# RockSat_PCB.net
KiCad netlist of a schematic drawn in EAGLE
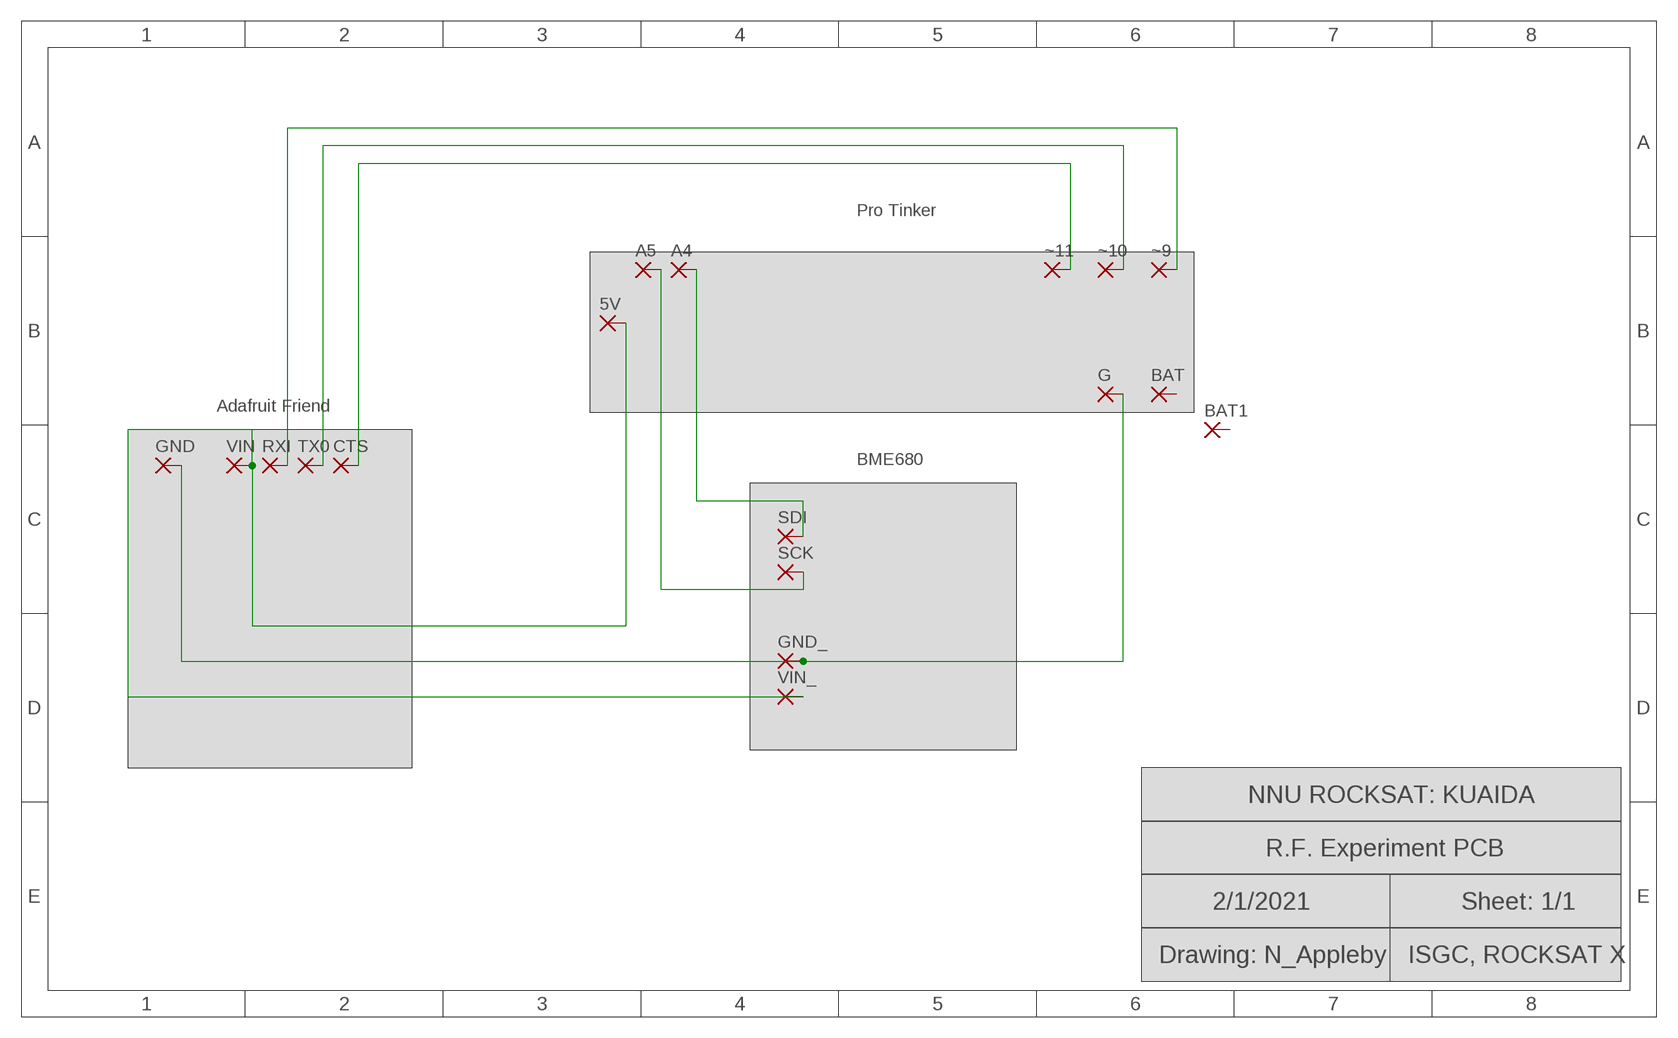
[diagram p0: schematic, sheet 1]

(export (version "E")
  (design (tool "Eeschema 10.0.6"))
  (components
    (comp (ref "5V")
      (value "1,6/0,9")
      (footprint "eagle-import:1,6_0,9")
      (libsource (lib "eagle-import") (part "1,6/0,9"))
    )
    (comp (ref "A4")
      (value "1,6/0,9")
      (footprint "eagle-import:1,6_0,9")
      (libsource (lib "eagle-import") (part "1,6/0,9"))
    )
    (comp (ref "A5")
      (value "1,6/0,9")
      (footprint "eagle-import:1,6_0,9")
      (libsource (lib "eagle-import") (part "1,6/0,9"))
    )
    (comp (ref "BAT")
      (value "1,6/0,9")
      (footprint "eagle-import:1,6_0,9")
      (libsource (lib "eagle-import") (part "1,6/0,9"))
    )
    (comp (ref "BAT1")
      (value "1,6/0,9")
      (footprint "eagle-import:1,6_0,9")
      (libsource (lib "eagle-import") (part "1,6/0,9"))
    )
    (comp (ref "CTS")
      (value "1,6/0,9")
      (footprint "eagle-import:1,6_0,9")
      (libsource (lib "eagle-import") (part "1,6/0,9"))
    )
    (comp (ref "G")
      (value "1,6/0,9")
      (footprint "eagle-import:1,6_0,9")
      (libsource (lib "eagle-import") (part "1,6/0,9"))
    )
    (comp (ref "GND")
      (value "1,6/0,9")
      (footprint "eagle-import:1,6_0,9")
      (libsource (lib "eagle-import") (part "1,6/0,9"))
    )
    (comp (ref "GND_")
      (value "1,6/0,9")
      (footprint "eagle-import:1,6_0,9")
      (libsource (lib "eagle-import") (part "1,6/0,9"))
    )
    (comp (ref "RXI")
      (value "1,6/0,9")
      (footprint "eagle-import:1,6_0,9")
      (libsource (lib "eagle-import") (part "1,6/0,9"))
    )
    (comp (ref "SCK")
      (value "1,6/0,9")
      (footprint "eagle-import:1,6_0,9")
      (libsource (lib "eagle-import") (part "1,6/0,9"))
    )
    (comp (ref "SDI")
      (value "1,6/0,9")
      (footprint "eagle-import:1,6_0,9")
      (libsource (lib "eagle-import") (part "1,6/0,9"))
    )
    (comp (ref "TX0")
      (value "1,6/0,9")
      (footprint "eagle-import:1,6_0,9")
      (libsource (lib "eagle-import") (part "1,6/0,9"))
    )
    (comp (ref "VIN")
      (value "1,6/0,9")
      (footprint "eagle-import:1,6_0,9")
      (libsource (lib "eagle-import") (part "1,6/0,9"))
    )
    (comp (ref "VIN_")
      (value "1,6/0,9")
      (footprint "eagle-import:1,6_0,9")
      (libsource (lib "eagle-import") (part "1,6/0,9"))
    )
    (comp (ref "~9")
      (value "1,6/0,9")
      (footprint "eagle-import:1,6_0,9")
      (libsource (lib "eagle-import") (part "1,6/0,9"))
    )
    (comp (ref "~10")
      (value "1,6/0,9")
      (footprint "eagle-import:1,6_0,9")
      (libsource (lib "eagle-import") (part "1,6/0,9"))
    )
    (comp (ref "~11")
      (value "1,6/0,9")
      (footprint "eagle-import:1,6_0,9")
      (libsource (lib "eagle-import") (part "1,6/0,9"))
    )
  )
  (nets
    (net (code "1") (name "Net-(5V-P)") (class "Default")
      (node (ref "5V") (pin "1") (pinfunction "P_1") (pintype "passive"))
      (node (ref "VIN") (pin "1") (pinfunction "P_1") (pintype "passive"))
      (node (ref "VIN_") (pin "1") (pinfunction "P_1") (pintype "passive"))
    )
    (net (code "2") (name "Net-(A4-P)") (class "Default")
      (node (ref "A4") (pin "1") (pinfunction "P_1") (pintype "passive"))
      (node (ref "SDI") (pin "1") (pinfunction "P_1") (pintype "passive"))
    )
    (net (code "3") (name "Net-(A5-P)") (class "Default")
      (node (ref "A5") (pin "1") (pinfunction "P_1") (pintype "passive"))
      (node (ref "SCK") (pin "1") (pinfunction "P_1") (pintype "passive"))
    )
    (net (code "4") (name "Net-(CTS-P)") (class "Default")
      (node (ref "CTS") (pin "1") (pinfunction "P_1") (pintype "passive"))
      (node (ref "~11") (pin "1") (pinfunction "P_1") (pintype "passive"))
    )
    (net (code "5") (name "Net-(G-P)") (class "Default")
      (node (ref "G") (pin "1") (pinfunction "P_1") (pintype "passive"))
      (node (ref "GND") (pin "1") (pinfunction "P_1") (pintype "passive"))
      (node (ref "GND_") (pin "1") (pinfunction "P_1") (pintype "passive"))
    )
    (net (code "6") (name "Net-(RXI-P)") (class "Default")
      (node (ref "RXI") (pin "1") (pinfunction "P_1") (pintype "passive"))
      (node (ref "~9") (pin "1") (pinfunction "P_1") (pintype "passive"))
    )
    (net (code "7") (name "Net-(TX0-P)") (class "Default")
      (node (ref "TX0") (pin "1") (pinfunction "P_1") (pintype "passive"))
      (node (ref "~10") (pin "1") (pinfunction "P_1") (pintype "passive"))
    )
    (net (code "8") (name "unconnected-(BAT-P-Pad1)") (class "Default")
      (node (ref "BAT") (pin "1") (pinfunction "P_1") (pintype "passive"))
    )
    (net (code "9") (name "unconnected-(BAT1-P-Pad1)") (class "Default")
      (node (ref "BAT1") (pin "1") (pinfunction "P_1") (pintype "passive"))
    )
  )
)
